# Decade_Box_Relay_Board.net
KiCad netlist of a schematic drawn in EAGLE
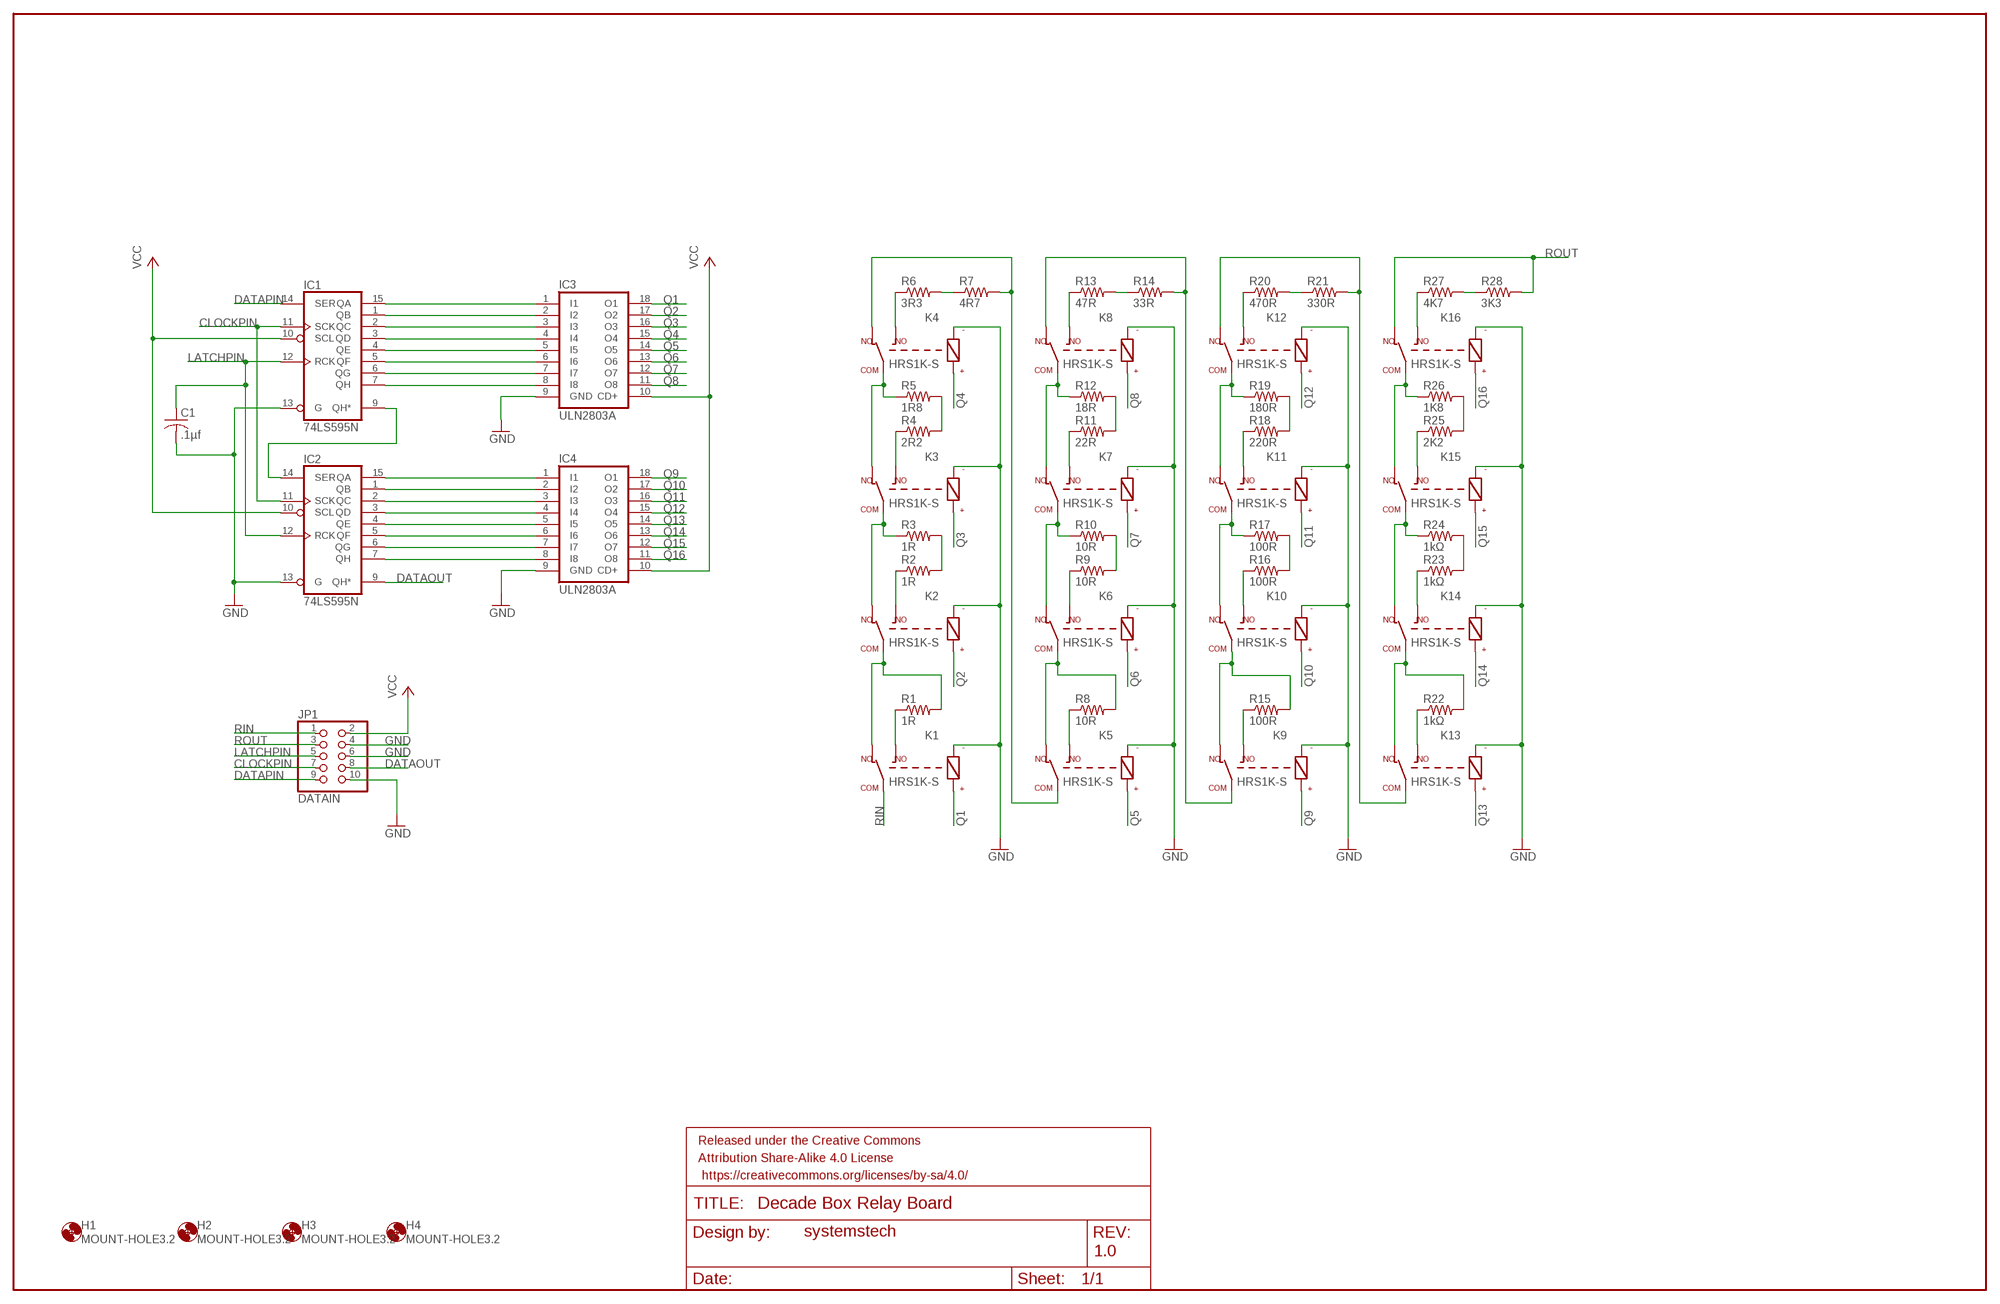
[diagram p0: schematic, sheet 1]

(export (version "E")
  (design (tool "Eeschema 10.0.6"))
  (components
    (comp (ref "C1")
      (value ".1µf")
      (footprint "eagle-import:C025-025X050")
      (libsource (lib "eagle-import") (part "C-US025-025X050"))
    )
    (comp (ref "FRAME1")
      (value "FRAME-LEDGER")
      (footprint "eagle-import:CREATIVE_COMMONS")
      (libsource (lib "eagle-import") (part "FRAME-LEDGER"))
    )
    (comp (ref "H1")
      (value "MOUNT-HOLE3.2")
      (footprint "eagle-import:3,2")
      (libsource (lib "eagle-import") (part "MOUNT-HOLE3.2"))
    )
    (comp (ref "H2")
      (value "MOUNT-HOLE3.2")
      (footprint "eagle-import:3,2")
      (libsource (lib "eagle-import") (part "MOUNT-HOLE3.2"))
    )
    (comp (ref "H3")
      (value "MOUNT-HOLE3.2")
      (footprint "eagle-import:3,2")
      (libsource (lib "eagle-import") (part "MOUNT-HOLE3.2"))
    )
    (comp (ref "H4")
      (value "MOUNT-HOLE3.2")
      (footprint "eagle-import:3,2")
      (libsource (lib "eagle-import") (part "MOUNT-HOLE3.2"))
    )
    (comp (ref "IC1")
      (value "74LS595N")
      (footprint "eagle-import:DIL16")
      (libsource (lib "eagle-import") (part "74595NLS"))
    )
    (comp (ref "IC2")
      (value "74LS595N")
      (footprint "eagle-import:DIL16")
      (libsource (lib "eagle-import") (part "74595NLS"))
    )
    (comp (ref "IC3")
      (value "ULN2803A")
      (footprint "eagle-import:DIL18")
      (libsource (lib "eagle-import") (part "ULN2803A"))
    )
    (comp (ref "IC4")
      (value "ULN2803A")
      (footprint "eagle-import:DIL18")
      (libsource (lib "eagle-import") (part "ULN2803A"))
    )
    (comp (ref "JP1")
      (value "DATAIN")
      (footprint "eagle-import:2X05")
      (libsource (lib "eagle-import") (part "PINHD-2X5"))
    )
    (comp (ref "K1")
      (value "HRS1K-S")
      (footprint "eagle-import:HRS1K-S")
      (libsource (lib "eagle-import") (part "HRS1K-S"))
    )
    (comp (ref "K2")
      (value "HRS1K-S")
      (footprint "eagle-import:HRS1K-S")
      (libsource (lib "eagle-import") (part "HRS1K-S"))
    )
    (comp (ref "K3")
      (value "HRS1K-S")
      (footprint "eagle-import:HRS1K-S")
      (libsource (lib "eagle-import") (part "HRS1K-S"))
    )
    (comp (ref "K4")
      (value "HRS1K-S")
      (footprint "eagle-import:HRS1K-S")
      (libsource (lib "eagle-import") (part "HRS1K-S"))
    )
    (comp (ref "K5")
      (value "HRS1K-S")
      (footprint "eagle-import:HRS1K-S")
      (libsource (lib "eagle-import") (part "HRS1K-S"))
    )
    (comp (ref "K6")
      (value "HRS1K-S")
      (footprint "eagle-import:HRS1K-S")
      (libsource (lib "eagle-import") (part "HRS1K-S"))
    )
    (comp (ref "K7")
      (value "HRS1K-S")
      (footprint "eagle-import:HRS1K-S")
      (libsource (lib "eagle-import") (part "HRS1K-S"))
    )
    (comp (ref "K8")
      (value "HRS1K-S")
      (footprint "eagle-import:HRS1K-S")
      (libsource (lib "eagle-import") (part "HRS1K-S"))
    )
    (comp (ref "K9")
      (value "HRS1K-S")
      (footprint "eagle-import:HRS1K-S")
      (libsource (lib "eagle-import") (part "HRS1K-S"))
    )
    (comp (ref "K10")
      (value "HRS1K-S")
      (footprint "eagle-import:HRS1K-S")
      (libsource (lib "eagle-import") (part "HRS1K-S"))
    )
    (comp (ref "K11")
      (value "HRS1K-S")
      (footprint "eagle-import:HRS1K-S")
      (libsource (lib "eagle-import") (part "HRS1K-S"))
    )
    (comp (ref "K12")
      (value "HRS1K-S")
      (footprint "eagle-import:HRS1K-S")
      (libsource (lib "eagle-import") (part "HRS1K-S"))
    )
    (comp (ref "K13")
      (value "HRS1K-S")
      (footprint "eagle-import:HRS1K-S")
      (libsource (lib "eagle-import") (part "HRS1K-S"))
    )
    (comp (ref "K14")
      (value "HRS1K-S")
      (footprint "eagle-import:HRS1K-S")
      (libsource (lib "eagle-import") (part "HRS1K-S"))
    )
    (comp (ref "K15")
      (value "HRS1K-S")
      (footprint "eagle-import:HRS1K-S")
      (libsource (lib "eagle-import") (part "HRS1K-S"))
    )
    (comp (ref "K16")
      (value "HRS1K-S")
      (footprint "eagle-import:HRS1K-S")
      (libsource (lib "eagle-import") (part "HRS1K-S"))
    )
    (comp (ref "R1")
      (value "1R")
      (footprint "eagle-import:0411_15")
      (libsource (lib "eagle-import") (part "R-US_0411/15"))
    )
    (comp (ref "R2")
      (value "1R")
      (footprint "eagle-import:0411_15")
      (libsource (lib "eagle-import") (part "R-US_0411/15"))
    )
    (comp (ref "R3")
      (value "1R")
      (footprint "eagle-import:0411_15")
      (libsource (lib "eagle-import") (part "R-US_0411/15"))
    )
    (comp (ref "R4")
      (value "2R2")
      (footprint "eagle-import:0411_15")
      (libsource (lib "eagle-import") (part "R-US_0411/15"))
    )
    (comp (ref "R5")
      (value "1R8")
      (footprint "eagle-import:0411_15")
      (libsource (lib "eagle-import") (part "R-US_0411/15"))
    )
    (comp (ref "R6")
      (value "3R3")
      (footprint "eagle-import:0411_15")
      (libsource (lib "eagle-import") (part "R-US_0411/15"))
    )
    (comp (ref "R7")
      (value "4R7")
      (footprint "eagle-import:0411_15")
      (libsource (lib "eagle-import") (part "R-US_0411/15"))
    )
    (comp (ref "R8")
      (value "10R")
      (footprint "eagle-import:0411_15")
      (libsource (lib "eagle-import") (part "R-US_0411/15"))
    )
    (comp (ref "R9")
      (value "10R")
      (footprint "eagle-import:0411_15")
      (libsource (lib "eagle-import") (part "R-US_0411/15"))
    )
    (comp (ref "R10")
      (value "10R")
      (footprint "eagle-import:0411_15")
      (libsource (lib "eagle-import") (part "R-US_0411/15"))
    )
    (comp (ref "R11")
      (value "22R")
      (footprint "eagle-import:0411_15")
      (libsource (lib "eagle-import") (part "R-US_0411/15"))
    )
    (comp (ref "R12")
      (value "18R")
      (footprint "eagle-import:0411_15")
      (libsource (lib "eagle-import") (part "R-US_0411/15"))
    )
    (comp (ref "R13")
      (value "47R")
      (footprint "eagle-import:0411_15")
      (libsource (lib "eagle-import") (part "R-US_0411/15"))
    )
    (comp (ref "R14")
      (value "33R")
      (footprint "eagle-import:0411_15")
      (libsource (lib "eagle-import") (part "R-US_0411/15"))
    )
    (comp (ref "R15")
      (value "100R")
      (footprint "eagle-import:0411_15")
      (libsource (lib "eagle-import") (part "R-US_0411/15"))
    )
    (comp (ref "R16")
      (value "100R")
      (footprint "eagle-import:0411_15")
      (libsource (lib "eagle-import") (part "R-US_0411/15"))
    )
    (comp (ref "R17")
      (value "100R")
      (footprint "eagle-import:0411_15")
      (libsource (lib "eagle-import") (part "R-US_0411/15"))
    )
    (comp (ref "R18")
      (value "220R")
      (footprint "eagle-import:0411_15")
      (libsource (lib "eagle-import") (part "R-US_0411/15"))
    )
    (comp (ref "R19")
      (value "180R")
      (footprint "eagle-import:0411_15")
      (libsource (lib "eagle-import") (part "R-US_0411/15"))
    )
    (comp (ref "R20")
      (value "470R")
      (footprint "eagle-import:0411_15")
      (libsource (lib "eagle-import") (part "R-US_0411/15"))
    )
    (comp (ref "R21")
      (value "330R")
      (footprint "eagle-import:0411_15")
      (libsource (lib "eagle-import") (part "R-US_0411/15"))
    )
    (comp (ref "R22")
      (value "1kΩ")
      (footprint "eagle-import:0411_15")
      (libsource (lib "eagle-import") (part "R-US_0411/15"))
    )
    (comp (ref "R23")
      (value "1kΩ")
      (footprint "eagle-import:0411_15")
      (libsource (lib "eagle-import") (part "R-US_0411/15"))
    )
    (comp (ref "R24")
      (value "1kΩ")
      (footprint "eagle-import:0411_15")
      (libsource (lib "eagle-import") (part "R-US_0411/15"))
    )
    (comp (ref "R25")
      (value "2K2")
      (footprint "eagle-import:0411_15")
      (libsource (lib "eagle-import") (part "R-US_0411/15"))
    )
    (comp (ref "R26")
      (value "1K8")
      (footprint "eagle-import:0411_15")
      (libsource (lib "eagle-import") (part "R-US_0411/15"))
    )
    (comp (ref "R27")
      (value "4K7")
      (footprint "eagle-import:0411_15")
      (libsource (lib "eagle-import") (part "R-US_0411/15"))
    )
    (comp (ref "R28")
      (value "3K3")
      (footprint "eagle-import:0411_15")
      (libsource (lib "eagle-import") (part "R-US_0411/15"))
    )
  )
  (nets
    (net (code "1") (name "/CLOCKPIN") (class "Default")
      (node (ref "IC1") (pin "11") (pinfunction "SCK_11") (pintype "input"))
      (node (ref "IC2") (pin "11") (pinfunction "SCK_11") (pintype "input"))
      (node (ref "JP1") (pin "7") (pinfunction "7_7") (pintype "passive"))
    )
    (net (code "2") (name "/DATAOUT") (class "Default")
      (node (ref "IC2") (pin "9") (pinfunction "QH*_9") (pintype "tri_state"))
      (node (ref "JP1") (pin "8") (pinfunction "8_8") (pintype "passive"))
    )
    (net (code "3") (name "/DATAPIN") (class "Default")
      (node (ref "IC1") (pin "14") (pinfunction "SER_14") (pintype "input"))
      (node (ref "JP1") (pin "9") (pinfunction "9_9") (pintype "passive"))
    )
    (net (code "4") (name "/LATCHPIN") (class "Default")
      (node (ref "C1") (pin "1") (pinfunction "1_1") (pintype "passive"))
      (node (ref "IC1") (pin "12") (pinfunction "RCK_12") (pintype "input"))
      (node (ref "IC2") (pin "12") (pinfunction "RCK_12") (pintype "input"))
      (node (ref "JP1") (pin "5") (pinfunction "5_5") (pintype "passive"))
    )
    (net (code "5") (name "/Q1") (class "Default")
      (node (ref "IC3") (pin "18") (pinfunction "O1_18") (pintype "open_collector"))
      (node (ref "K1") (pin "P$2") (pinfunction "2_P$2") (pintype "passive"))
    )
    (net (code "6") (name "/Q2") (class "Default")
      (node (ref "IC3") (pin "17") (pinfunction "O2_17") (pintype "open_collector"))
      (node (ref "K2") (pin "P$2") (pinfunction "2_P$2") (pintype "passive"))
    )
    (net (code "7") (name "/Q3") (class "Default")
      (node (ref "IC3") (pin "16") (pinfunction "O3_16") (pintype "open_collector"))
      (node (ref "K3") (pin "P$2") (pinfunction "2_P$2") (pintype "passive"))
    )
    (net (code "8") (name "/Q4") (class "Default")
      (node (ref "IC3") (pin "15") (pinfunction "O4_15") (pintype "open_collector"))
      (node (ref "K4") (pin "P$2") (pinfunction "2_P$2") (pintype "passive"))
    )
    (net (code "9") (name "/Q5") (class "Default")
      (node (ref "IC3") (pin "14") (pinfunction "O5_14") (pintype "open_collector"))
      (node (ref "K5") (pin "P$2") (pinfunction "2_P$2") (pintype "passive"))
    )
    (net (code "10") (name "/Q6") (class "Default")
      (node (ref "IC3") (pin "13") (pinfunction "O6_13") (pintype "open_collector"))
      (node (ref "K6") (pin "P$2") (pinfunction "2_P$2") (pintype "passive"))
    )
    (net (code "11") (name "/Q7") (class "Default")
      (node (ref "IC3") (pin "12") (pinfunction "O7_12") (pintype "open_collector"))
      (node (ref "K7") (pin "P$2") (pinfunction "2_P$2") (pintype "passive"))
    )
    (net (code "12") (name "/Q8") (class "Default")
      (node (ref "IC3") (pin "11") (pinfunction "O8_11") (pintype "open_collector"))
      (node (ref "K8") (pin "P$2") (pinfunction "2_P$2") (pintype "passive"))
    )
    (net (code "13") (name "/Q9") (class "Default")
      (node (ref "IC4") (pin "18") (pinfunction "O1_18") (pintype "open_collector"))
      (node (ref "K9") (pin "P$2") (pinfunction "2_P$2") (pintype "passive"))
    )
    (net (code "14") (name "/Q10") (class "Default")
      (node (ref "IC4") (pin "17") (pinfunction "O2_17") (pintype "open_collector"))
      (node (ref "K10") (pin "P$2") (pinfunction "2_P$2") (pintype "passive"))
    )
    (net (code "15") (name "/Q11") (class "Default")
      (node (ref "IC4") (pin "16") (pinfunction "O3_16") (pintype "open_collector"))
      (node (ref "K11") (pin "P$2") (pinfunction "2_P$2") (pintype "passive"))
    )
    (net (code "16") (name "/Q12") (class "Default")
      (node (ref "IC4") (pin "15") (pinfunction "O4_15") (pintype "open_collector"))
      (node (ref "K12") (pin "P$2") (pinfunction "2_P$2") (pintype "passive"))
    )
    (net (code "17") (name "/Q13") (class "Default")
      (node (ref "IC4") (pin "14") (pinfunction "O5_14") (pintype "open_collector"))
      (node (ref "K13") (pin "P$2") (pinfunction "2_P$2") (pintype "passive"))
    )
    (net (code "18") (name "/Q14") (class "Default")
      (node (ref "IC4") (pin "13") (pinfunction "O6_13") (pintype "open_collector"))
      (node (ref "K14") (pin "P$2") (pinfunction "2_P$2") (pintype "passive"))
    )
    (net (code "19") (name "/Q15") (class "Default")
      (node (ref "IC4") (pin "12") (pinfunction "O7_12") (pintype "open_collector"))
      (node (ref "K15") (pin "P$2") (pinfunction "2_P$2") (pintype "passive"))
    )
    (net (code "20") (name "/Q16") (class "Default")
      (node (ref "IC4") (pin "11") (pinfunction "O8_11") (pintype "open_collector"))
      (node (ref "K16") (pin "P$2") (pinfunction "2_P$2") (pintype "passive"))
    )
    (net (code "21") (name "/RIN") (class "Default")
      (node (ref "JP1") (pin "1") (pinfunction "1_1") (pintype "passive"))
      (node (ref "K1") (pin "P$1") (pinfunction "1_P$1") (pintype "passive"))
    )
    (net (code "22") (name "/ROUT") (class "Default")
      (node (ref "JP1") (pin "3") (pinfunction "3_3") (pintype "passive"))
      (node (ref "K16") (pin "P$5") (pinfunction "5_P$5") (pintype "passive"))
      (node (ref "R28") (pin "2") (pinfunction "2_2") (pintype "passive"))
    )
    (net (code "23") (name "GND") (class "Default")
      (node (ref "C1") (pin "2") (pinfunction "2_2") (pintype "passive"))
      (node (ref "IC1") (pin "13") (pinfunction "G_13") (pintype "input"))
      (node (ref "IC2") (pin "13") (pinfunction "G_13") (pintype "input"))
      (node (ref "IC3") (pin "9") (pinfunction "GND_9") (pintype "power_in"))
      (node (ref "IC4") (pin "9") (pinfunction "GND_9") (pintype "power_in"))
      (node (ref "JP1") (pin "10") (pinfunction "10_10") (pintype "passive"))
      (node (ref "JP1") (pin "4") (pinfunction "4_4") (pintype "passive"))
      (node (ref "JP1") (pin "6") (pinfunction "6_6") (pintype "passive"))
      (node (ref "K1") (pin "P$3") (pinfunction "3_P$3") (pintype "passive"))
      (node (ref "K10") (pin "P$3") (pinfunction "3_P$3") (pintype "passive"))
      (node (ref "K11") (pin "P$3") (pinfunction "3_P$3") (pintype "passive"))
      (node (ref "K12") (pin "P$3") (pinfunction "3_P$3") (pintype "passive"))
      (node (ref "K13") (pin "P$3") (pinfunction "3_P$3") (pintype "passive"))
      (node (ref "K14") (pin "P$3") (pinfunction "3_P$3") (pintype "passive"))
      (node (ref "K15") (pin "P$3") (pinfunction "3_P$3") (pintype "passive"))
      (node (ref "K16") (pin "P$3") (pinfunction "3_P$3") (pintype "passive"))
      (node (ref "K2") (pin "P$3") (pinfunction "3_P$3") (pintype "passive"))
      (node (ref "K3") (pin "P$3") (pinfunction "3_P$3") (pintype "passive"))
      (node (ref "K4") (pin "P$3") (pinfunction "3_P$3") (pintype "passive"))
      (node (ref "K5") (pin "P$3") (pinfunction "3_P$3") (pintype "passive"))
      (node (ref "K6") (pin "P$3") (pinfunction "3_P$3") (pintype "passive"))
      (node (ref "K7") (pin "P$3") (pinfunction "3_P$3") (pintype "passive"))
      (node (ref "K8") (pin "P$3") (pinfunction "3_P$3") (pintype "passive"))
      (node (ref "K9") (pin "P$3") (pinfunction "3_P$3") (pintype "passive"))
    )
    (net (code "24") (name "Net-(IC1A-QA)") (class "Default")
      (node (ref "IC1") (pin "15") (pinfunction "QA_15") (pintype "tri_state"))
      (node (ref "IC3") (pin "1") (pinfunction "I1_1") (pintype "input"))
    )
    (net (code "25") (name "Net-(IC1A-QB)") (class "Default")
      (node (ref "IC1") (pin "1") (pinfunction "QB_1") (pintype "tri_state"))
      (node (ref "IC3") (pin "2") (pinfunction "I2_2") (pintype "input"))
    )
    (net (code "26") (name "Net-(IC1A-QC)") (class "Default")
      (node (ref "IC1") (pin "2") (pinfunction "QC_2") (pintype "tri_state"))
      (node (ref "IC3") (pin "3") (pinfunction "I3_3") (pintype "input"))
    )
    (net (code "27") (name "Net-(IC1A-QD)") (class "Default")
      (node (ref "IC1") (pin "3") (pinfunction "QD_3") (pintype "tri_state"))
      (node (ref "IC3") (pin "4") (pinfunction "I4_4") (pintype "input"))
    )
    (net (code "28") (name "Net-(IC1A-QE)") (class "Default")
      (node (ref "IC1") (pin "4") (pinfunction "QE_4") (pintype "tri_state"))
      (node (ref "IC3") (pin "5") (pinfunction "I5_5") (pintype "input"))
    )
    (net (code "29") (name "Net-(IC1A-QF)") (class "Default")
      (node (ref "IC1") (pin "5") (pinfunction "QF_5") (pintype "tri_state"))
      (node (ref "IC3") (pin "6") (pinfunction "I6_6") (pintype "input"))
    )
    (net (code "30") (name "Net-(IC1A-QG)") (class "Default")
      (node (ref "IC1") (pin "6") (pinfunction "QG_6") (pintype "tri_state"))
      (node (ref "IC3") (pin "7") (pinfunction "I7_7") (pintype "input"))
    )
    (net (code "31") (name "Net-(IC1A-QH)") (class "Default")
      (node (ref "IC1") (pin "7") (pinfunction "QH_7") (pintype "tri_state"))
      (node (ref "IC3") (pin "8") (pinfunction "I8_8") (pintype "input"))
    )
    (net (code "32") (name "Net-(IC1A-QH*)") (class "Default")
      (node (ref "IC1") (pin "9") (pinfunction "QH*_9") (pintype "tri_state"))
      (node (ref "IC2") (pin "14") (pinfunction "SER_14") (pintype "input"))
    )
    (net (code "33") (name "Net-(IC2A-QA)") (class "Default")
      (node (ref "IC2") (pin "15") (pinfunction "QA_15") (pintype "tri_state"))
      (node (ref "IC4") (pin "1") (pinfunction "I1_1") (pintype "input"))
    )
    (net (code "34") (name "Net-(IC2A-QB)") (class "Default")
      (node (ref "IC2") (pin "1") (pinfunction "QB_1") (pintype "tri_state"))
      (node (ref "IC4") (pin "2") (pinfunction "I2_2") (pintype "input"))
    )
    (net (code "35") (name "Net-(IC2A-QC)") (class "Default")
      (node (ref "IC2") (pin "2") (pinfunction "QC_2") (pintype "tri_state"))
      (node (ref "IC4") (pin "3") (pinfunction "I3_3") (pintype "input"))
    )
    (net (code "36") (name "Net-(IC2A-QD)") (class "Default")
      (node (ref "IC2") (pin "3") (pinfunction "QD_3") (pintype "tri_state"))
      (node (ref "IC4") (pin "4") (pinfunction "I4_4") (pintype "input"))
    )
    (net (code "37") (name "Net-(IC2A-QE)") (class "Default")
      (node (ref "IC2") (pin "4") (pinfunction "QE_4") (pintype "tri_state"))
      (node (ref "IC4") (pin "5") (pinfunction "I5_5") (pintype "input"))
    )
    (net (code "38") (name "Net-(IC2A-QF)") (class "Default")
      (node (ref "IC2") (pin "5") (pinfunction "QF_5") (pintype "tri_state"))
      (node (ref "IC4") (pin "6") (pinfunction "I6_6") (pintype "input"))
    )
    (net (code "39") (name "Net-(IC2A-QG)") (class "Default")
      (node (ref "IC2") (pin "6") (pinfunction "QG_6") (pintype "tri_state"))
      (node (ref "IC4") (pin "7") (pinfunction "I7_7") (pintype "input"))
    )
    (net (code "40") (name "Net-(IC2A-QH)") (class "Default")
      (node (ref "IC2") (pin "7") (pinfunction "QH_7") (pintype "tri_state"))
      (node (ref "IC4") (pin "8") (pinfunction "I8_8") (pintype "input"))
    )
    (net (code "41") (name "Net-(K1-4)") (class "Default")
      (node (ref "K1") (pin "P$4") (pinfunction "4_P$4") (pintype "passive"))
      (node (ref "R1") (pin "1") (pinfunction "1_1") (pintype "passive"))
    )
    (net (code "42") (name "Net-(K1-5)") (class "Default")
      (node (ref "K1") (pin "P$5") (pinfunction "5_P$5") (pintype "passive"))
      (node (ref "K2") (pin "P$1") (pinfunction "1_P$1") (pintype "passive"))
      (node (ref "R1") (pin "2") (pinfunction "2_2") (pintype "passive"))
    )
    (net (code "43") (name "Net-(K2-4)") (class "Default")
      (node (ref "K2") (pin "P$4") (pinfunction "4_P$4") (pintype "passive"))
      (node (ref "R2") (pin "1") (pinfunction "1_1") (pintype "passive"))
    )
    (net (code "44") (name "Net-(K2-5)") (class "Default")
      (node (ref "K2") (pin "P$5") (pinfunction "5_P$5") (pintype "passive"))
      (node (ref "K3") (pin "P$1") (pinfunction "1_P$1") (pintype "passive"))
      (node (ref "R3") (pin "1") (pinfunction "1_1") (pintype "passive"))
    )
    (net (code "45") (name "Net-(K3-4)") (class "Default")
      (node (ref "K3") (pin "P$4") (pinfunction "4_P$4") (pintype "passive"))
      (node (ref "R4") (pin "1") (pinfunction "1_1") (pintype "passive"))
    )
    (net (code "46") (name "Net-(K3-5)") (class "Default")
      (node (ref "K3") (pin "P$5") (pinfunction "5_P$5") (pintype "passive"))
      (node (ref "K4") (pin "P$1") (pinfunction "1_P$1") (pintype "passive"))
      (node (ref "R5") (pin "1") (pinfunction "1_1") (pintype "passive"))
    )
    (net (code "47") (name "Net-(K4-4)") (class "Default")
      (node (ref "K4") (pin "P$4") (pinfunction "4_P$4") (pintype "passive"))
      (node (ref "R6") (pin "1") (pinfunction "1_1") (pintype "passive"))
    )
    (net (code "48") (name "Net-(K4-5)") (class "Default")
      (node (ref "K4") (pin "P$5") (pinfunction "5_P$5") (pintype "passive"))
      (node (ref "K5") (pin "P$1") (pinfunction "1_P$1") (pintype "passive"))
      (node (ref "R7") (pin "2") (pinfunction "2_2") (pintype "passive"))
    )
    (net (code "49") (name "Net-(K5-4)") (class "Default")
      (node (ref "K5") (pin "P$4") (pinfunction "4_P$4") (pintype "passive"))
      (node (ref "R8") (pin "1") (pinfunction "1_1") (pintype "passive"))
    )
    (net (code "50") (name "Net-(K5-5)") (class "Default")
      (node (ref "K5") (pin "P$5") (pinfunction "5_P$5") (pintype "passive"))
      (node (ref "K6") (pin "P$1") (pinfunction "1_P$1") (pintype "passive"))
      (node (ref "R8") (pin "2") (pinfunction "2_2") (pintype "passive"))
    )
    (net (code "51") (name "Net-(K6-4)") (class "Default")
      (node (ref "K6") (pin "P$4") (pinfunction "4_P$4") (pintype "passive"))
      (node (ref "R9") (pin "1") (pinfunction "1_1") (pintype "passive"))
    )
    (net (code "52") (name "Net-(K6-5)") (class "Default")
      (node (ref "K6") (pin "P$5") (pinfunction "5_P$5") (pintype "passive"))
      (node (ref "K7") (pin "P$1") (pinfunction "1_P$1") (pintype "passive"))
      (node (ref "R10") (pin "1") (pinfunction "1_1") (pintype "passive"))
    )
    (net (code "53") (name "Net-(K7-4)") (class "Default")
      (node (ref "K7") (pin "P$4") (pinfunction "4_P$4") (pintype "passive"))
      (node (ref "R11") (pin "1") (pinfunction "1_1") (pintype "passive"))
    )
    (net (code "54") (name "Net-(K7-5)") (class "Default")
      (node (ref "K7") (pin "P$5") (pinfunction "5_P$5") (pintype "passive"))
      (node (ref "K8") (pin "P$1") (pinfunction "1_P$1") (pintype "passive"))
      (node (ref "R12") (pin "1") (pinfunction "1_1") (pintype "passive"))
    )
    (net (code "55") (name "Net-(K8-4)") (class "Default")
      (node (ref "K8") (pin "P$4") (pinfunction "4_P$4") (pintype "passive"))
      (node (ref "R13") (pin "1") (pinfunction "1_1") (pintype "passive"))
    )
    (net (code "56") (name "Net-(K8-5)") (class "Default")
      (node (ref "K8") (pin "P$5") (pinfunction "5_P$5") (pintype "passive"))
      (node (ref "K9") (pin "P$1") (pinfunction "1_P$1") (pintype "passive"))
      (node (ref "R14") (pin "2") (pinfunction "2_2") (pintype "passive"))
    )
    (net (code "57") (name "Net-(K9-4)") (class "Default")
      (node (ref "K9") (pin "P$4") (pinfunction "4_P$4") (pintype "passive"))
      (node (ref "R15") (pin "1") (pinfunction "1_1") (pintype "passive"))
    )
    (net (code "58") (name "Net-(K10-1)") (class "Default")
      (node (ref "K10") (pin "P$1") (pinfunction "1_P$1") (pintype "passive"))
      (node (ref "K9") (pin "P$5") (pinfunction "5_P$5") (pintype "passive"))
      (node (ref "R15") (pin "2") (pinfunction "2_2") (pintype "passive"))
    )
    (net (code "59") (name "Net-(K10-4)") (class "Default")
      (node (ref "K10") (pin "P$4") (pinfunction "4_P$4") (pintype "passive"))
      (node (ref "R16") (pin "1") (pinfunction "1_1") (pintype "passive"))
    )
    (net (code "60") (name "Net-(K10-5)") (class "Default")
      (node (ref "K10") (pin "P$5") (pinfunction "5_P$5") (pintype "passive"))
      (node (ref "K11") (pin "P$1") (pinfunction "1_P$1") (pintype "passive"))
      (node (ref "R17") (pin "1") (pinfunction "1_1") (pintype "passive"))
    )
    (net (code "61") (name "Net-(K11-4)") (class "Default")
      (node (ref "K11") (pin "P$4") (pinfunction "4_P$4") (pintype "passive"))
      (node (ref "R18") (pin "1") (pinfunction "1_1") (pintype "passive"))
    )
    (net (code "62") (name "Net-(K11-5)") (class "Default")
      (node (ref "K11") (pin "P$5") (pinfunction "5_P$5") (pintype "passive"))
      (node (ref "K12") (pin "P$1") (pinfunction "1_P$1") (pintype "passive"))
      (node (ref "R19") (pin "1") (pinfunction "1_1") (pintype "passive"))
    )
    (net (code "63") (name "Net-(K12-4)") (class "Default")
      (node (ref "K12") (pin "P$4") (pinfunction "4_P$4") (pintype "passive"))
      (node (ref "R20") (pin "1") (pinfunction "1_1") (pintype "passive"))
    )
    (net (code "64") (name "Net-(K12-5)") (class "Default")
      (node (ref "K12") (pin "P$5") (pinfunction "5_P$5") (pintype "passive"))
      (node (ref "K13") (pin "P$1") (pinfunction "1_P$1") (pintype "passive"))
      (node (ref "R21") (pin "2") (pinfunction "2_2") (pintype "passive"))
    )
    (net (code "65") (name "Net-(K13-4)") (class "Default")
      (node (ref "K13") (pin "P$4") (pinfunction "4_P$4") (pintype "passive"))
      (node (ref "R22") (pin "1") (pinfunction "1_1") (pintype "passive"))
    )
    (net (code "66") (name "Net-(K13-5)") (class "Default")
      (node (ref "K13") (pin "P$5") (pinfunction "5_P$5") (pintype "passive"))
      (node (ref "K14") (pin "P$1") (pinfunction "1_P$1") (pintype "passive"))
      (node (ref "R22") (pin "2") (pinfunction "2_2") (pintype "passive"))
    )
    (net (code "67") (name "Net-(K14-4)") (class "Default")
      (node (ref "K14") (pin "P$4") (pinfunction "4_P$4") (pintype "passive"))
      (node (ref "R23") (pin "1") (pinfunction "1_1") (pintype "passive"))
    )
    (net (code "68") (name "Net-(K14-5)") (class "Default")
      (node (ref "K14") (pin "P$5") (pinfunction "5_P$5") (pintype "passive"))
      (node (ref "K15") (pin "P$1") (pinfunction "1_P$1") (pintype "passive"))
      (node (ref "R24") (pin "1") (pinfunction "1_1") (pintype "passive"))
    )
    (net (code "69") (name "Net-(K15-4)") (class "Default")
      (node (ref "K15") (pin "P$4") (pinfunction "4_P$4") (pintype "passive"))
      (node (ref "R25") (pin "1") (pinfunction "1_1") (pintype "passive"))
    )
    (net (code "70") (name "Net-(K15-5)") (class "Default")
      (node (ref "K15") (pin "P$5") (pinfunction "5_P$5") (pintype "passive"))
      (node (ref "K16") (pin "P$1") (pinfunction "1_P$1") (pintype "passive"))
      (node (ref "R26") (pin "1") (pinfunction "1_1") (pintype "passive"))
    )
    (net (code "71") (name "Net-(K16-4)") (class "Default")
      (node (ref "K16") (pin "P$4") (pinfunction "4_P$4") (pintype "passive"))
      (node (ref "R27") (pin "1") (pinfunction "1_1") (pintype "passive"))
    )
    (net (code "72") (name "Net-(R2-Pad2)") (class "Default")
      (node (ref "R2") (pin "2") (pinfunction "2_2") (pintype "passive"))
      (node (ref "R3") (pin "2") (pinfunction "2_2") (pintype "passive"))
    )
    (net (code "73") (name "Net-(R4-Pad2)") (class "Default")
      (node (ref "R4") (pin "2") (pinfunction "2_2") (pintype "passive"))
      (node (ref "R5") (pin "2") (pinfunction "2_2") (pintype "passive"))
    )
    (net (code "74") (name "Net-(R6-Pad2)") (class "Default")
      (node (ref "R6") (pin "2") (pinfunction "2_2") (pintype "passive"))
      (node (ref "R7") (pin "1") (pinfunction "1_1") (pintype "passive"))
    )
    (net (code "75") (name "Net-(R10-Pad2)") (class "Default")
      (node (ref "R10") (pin "2") (pinfunction "2_2") (pintype "passive"))
      (node (ref "R9") (pin "2") (pinfunction "2_2") (pintype "passive"))
    )
    (net (code "76") (name "Net-(R11-Pad2)") (class "Default")
      (node (ref "R11") (pin "2") (pinfunction "2_2") (pintype "passive"))
      (node (ref "R12") (pin "2") (pinfunction "2_2") (pintype "passive"))
    )
    (net (code "77") (name "Net-(R13-Pad2)") (class "Default")
      (node (ref "R13") (pin "2") (pinfunction "2_2") (pintype "passive"))
      (node (ref "R14") (pin "1") (pinfunction "1_1") (pintype "passive"))
    )
    (net (code "78") (name "Net-(R16-Pad2)") (class "Default")
      (node (ref "R16") (pin "2") (pinfunction "2_2") (pintype "passive"))
      (node (ref "R17") (pin "2") (pinfunction "2_2") (pintype "passive"))
    )
    (net (code "79") (name "Net-(R18-Pad2)") (class "Default")
      (node (ref "R18") (pin "2") (pinfunction "2_2") (pintype "passive"))
      (node (ref "R19") (pin "2") (pinfunction "2_2") (pintype "passive"))
    )
    (net (code "80") (name "Net-(R20-Pad2)") (class "Default")
      (node (ref "R20") (pin "2") (pinfunction "2_2") (pintype "passive"))
      (node (ref "R21") (pin "1") (pinfunction "1_1") (pintype "passive"))
    )
    (net (code "81") (name "Net-(R23-Pad2)") (class "Default")
      (node (ref "R23") (pin "2") (pinfunction "2_2") (pintype "passive"))
      (node (ref "R24") (pin "2") (pinfunction "2_2") (pintype "passive"))
    )
    (net (code "82") (name "Net-(R25-Pad2)") (class "Default")
      (node (ref "R25") (pin "2") (pinfunction "2_2") (pintype "passive"))
      (node (ref "R26") (pin "2") (pinfunction "2_2") (pintype "passive"))
    )
    (net (code "83") (name "Net-(R27-Pad2)") (class "Default")
      (node (ref "R27") (pin "2") (pinfunction "2_2") (pintype "passive"))
      (node (ref "R28") (pin "1") (pinfunction "1_1") (pintype "passive"))
    )
    (net (code "84") (name "VCC") (class "Default")
      (node (ref "IC1") (pin "10") (pinfunction "SCL_10") (pintype "input"))
      (node (ref "IC2") (pin "10") (pinfunction "SCL_10") (pintype "input"))
      (node (ref "IC3") (pin "10") (pinfunction "CD+_10") (pintype "passive"))
      (node (ref "IC4") (pin "10") (pinfunction "CD+_10") (pintype "passive"))
      (node (ref "JP1") (pin "2") (pinfunction "2_2") (pintype "passive"))
    )
  )
)
